# Mako_DSP_Power_R1_2.net
KiCad netlist of a schematic drawn in Altium Designer
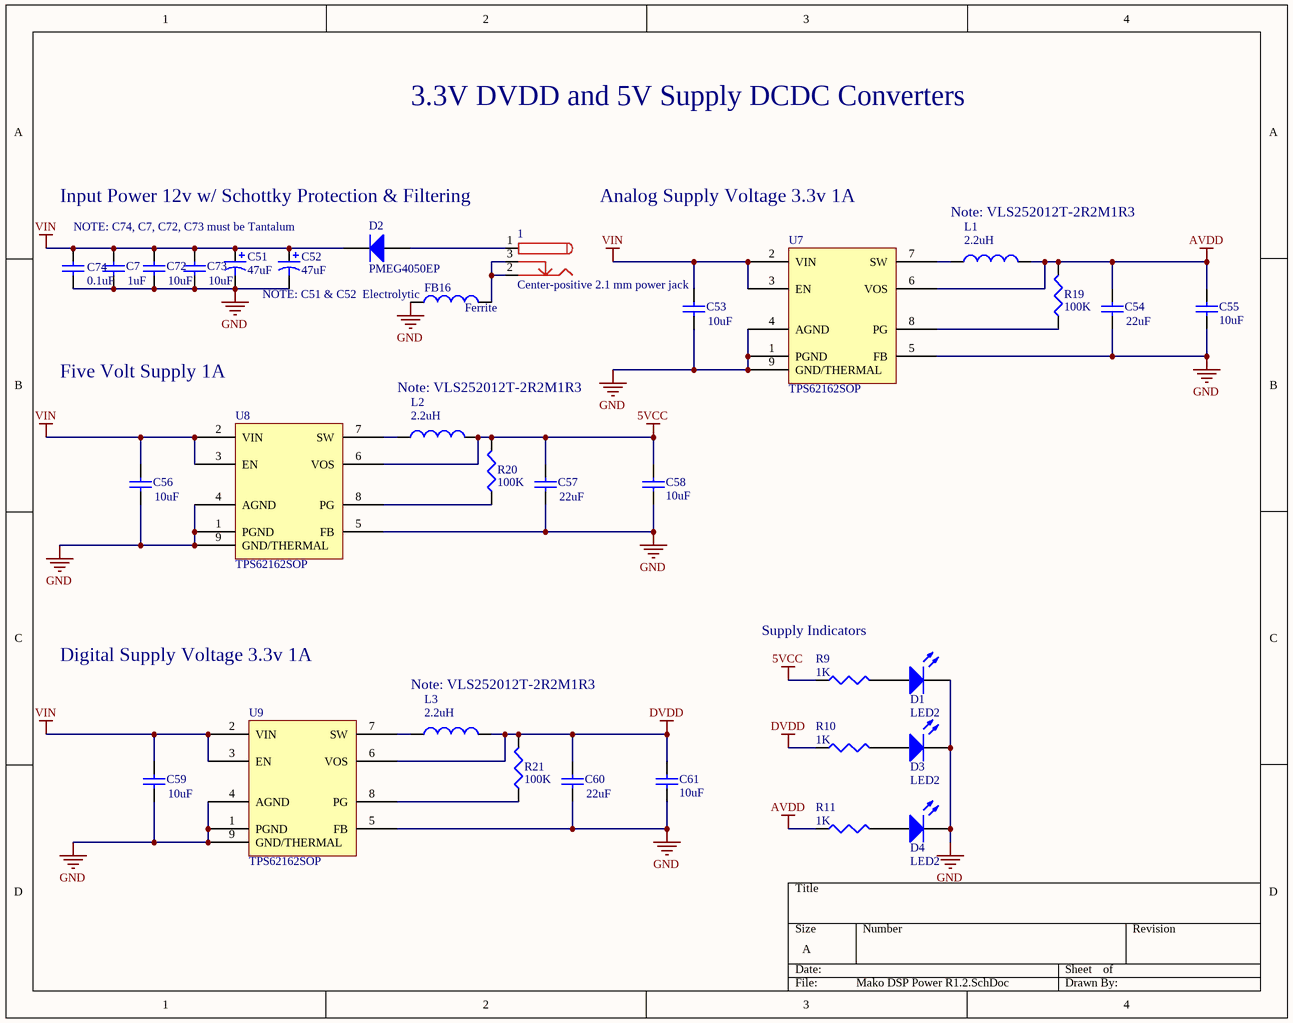
[diagram p0: Mako DSP Power R1.2.SchDoc]

(export (version "E")
  (design (tool "Eeschema 10.0.6"))
  (components
    (comp (ref "1")
      (value "Center-positive 2.1 mm power jack")
      (footprint "PJ-102AH")
      (description "Power jack")
      (fields (field (name "PUBLISHER") "Altium Limited"))
      (libsource (lib "Rascal") (part "PWR2.5"))
    )
    (comp (ref "C7")
      (value "1uF")
      (footprint "C1206")
      (description "Capacitor (Semiconductor SIM Model)")
      (fields (field (name "Comment") "Cap Semi") (field (name "PUBLISHER") "Altium Limited"))
      (libsource (lib "Miscellaneous Devices") (part "Cap Semi"))
    )
    (comp (ref "C51")
      (value "47uF")
      (footprint "CAPPR2.5-6.3x5")
      (description "Polarized Capacitor (Radial)")
      (fields (field (name "Comment") "Cap Pol1") (field (name "PUBLISHER") "Altium Limited"))
      (libsource (lib "Miscellaneous Devices") (part "Cap Pol1"))
    )
    (comp (ref "C52")
      (value "47uF")
      (footprint "CAPPR2.5-6.3x5")
      (description "Polarized Capacitor (Radial)")
      (fields (field (name "Comment") "Cap Pol1") (field (name "PUBLISHER") "Altium Limited"))
      (libsource (lib "Miscellaneous Devices") (part "Cap Pol1"))
    )
    (comp (ref "C53")
      (value "10uF")
      (footprint "C1206")
      (description "Capacitor (Semiconductor SIM Model)")
      (fields (field (name "Comment") "Cap Semi") (field (name "PUBLISHER") "Altium Limited"))
      (libsource (lib "Miscellaneous Devices") (part "Cap Semi"))
    )
    (comp (ref "C54")
      (value "22uF")
      (footprint "C1206")
      (description "Capacitor (Semiconductor SIM Model)")
      (fields (field (name "Comment") "Cap Semi") (field (name "PUBLISHER") "Altium Limited"))
      (libsource (lib "Miscellaneous Devices") (part "Cap Semi"))
    )
    (comp (ref "C55")
      (value "10uF")
      (footprint "Panasonic VS B")
      (description "Capacitor (Semiconductor SIM Model)")
      (fields (field (name "Comment") "Cap Semi") (field (name "PUBLISHER") "Altium Limited"))
      (libsource (lib "Miscellaneous Devices") (part "Cap Semi"))
    )
    (comp (ref "C56")
      (value "10uF")
      (footprint "C1206")
      (description "Capacitor (Semiconductor SIM Model)")
      (fields (field (name "Comment") "Cap Semi") (field (name "PUBLISHER") "Altium Limited"))
      (libsource (lib "Miscellaneous Devices") (part "Cap Semi"))
    )
    (comp (ref "C57")
      (value "22uF")
      (footprint "C1206")
      (description "Capacitor (Semiconductor SIM Model)")
      (fields (field (name "Comment") "Cap Semi") (field (name "PUBLISHER") "Altium Limited"))
      (libsource (lib "Miscellaneous Devices") (part "Cap Semi"))
    )
    (comp (ref "C58")
      (value "10uF")
      (footprint "Panasonic VS B")
      (description "Capacitor (Semiconductor SIM Model)")
      (fields (field (name "Comment") "Cap Semi") (field (name "PUBLISHER") "Altium Limited"))
      (libsource (lib "Miscellaneous Devices") (part "Cap Semi"))
    )
    (comp (ref "C59")
      (value "10uF")
      (footprint "C1206")
      (description "Capacitor (Semiconductor SIM Model)")
      (fields (field (name "Comment") "Cap Semi") (field (name "PUBLISHER") "Altium Limited"))
      (libsource (lib "Miscellaneous Devices") (part "Cap Semi"))
    )
    (comp (ref "C60")
      (value "22uF")
      (footprint "C1206")
      (description "Capacitor (Semiconductor SIM Model)")
      (fields (field (name "Comment") "Cap Semi") (field (name "PUBLISHER") "Altium Limited"))
      (libsource (lib "Miscellaneous Devices") (part "Cap Semi"))
    )
    (comp (ref "C61")
      (value "10uF")
      (footprint "Panasonic VS B")
      (description "Capacitor (Semiconductor SIM Model)")
      (fields (field (name "Comment") "Cap Semi") (field (name "PUBLISHER") "Altium Limited"))
      (libsource (lib "Miscellaneous Devices") (part "Cap Semi"))
    )
    (comp (ref "C72")
      (value "10uF")
      (footprint "C1206")
      (description "Capacitor (Semiconductor SIM Model)")
      (fields (field (name "Comment") "Cap Semi") (field (name "PUBLISHER") "Altium Limited"))
      (libsource (lib "Miscellaneous Devices") (part "Cap Semi"))
    )
    (comp (ref "C73")
      (value "10uF")
      (footprint "C1206")
      (description "Capacitor (Semiconductor SIM Model)")
      (fields (field (name "Comment") "Cap Semi") (field (name "PUBLISHER") "Altium Limited"))
      (libsource (lib "Miscellaneous Devices") (part "Cap Semi"))
    )
    (comp (ref "C74")
      (value "0.1uF")
      (footprint "C1206")
      (description "Capacitor (Semiconductor SIM Model)")
      (fields (field (name "Comment") "Cap Semi") (field (name "PUBLISHER") "Altium Limited"))
      (libsource (lib "Miscellaneous Devices") (part "Cap Semi"))
    )
    (comp (ref "D1")
      (value "LED2")
      (footprint "SM 0805 polarized")
      (description "Typical RED, GREEN, YELLOW, AMBER GaAs LED")
      (fields (field (name "PUBLISHER") "Altium Limited"))
      (libsource (lib "Miscellaneous Devices") (part "LED2"))
    )
    (comp (ref "D2")
      (value "PMEG4050EP")
      (footprint "PMEG4050EP")
      (description "Default Diode")
      (fields (field (name "PUBLISHER") "Altium Limited"))
      (libsource (lib "Miscellaneous Devices") (part "Diode"))
    )
    (comp (ref "D3")
      (value "LED2")
      (footprint "SM 0805 polarized")
      (description "Typical RED, GREEN, YELLOW, AMBER GaAs LED")
      (fields (field (name "PUBLISHER") "Altium Limited"))
      (libsource (lib "Miscellaneous Devices") (part "LED2"))
    )
    (comp (ref "D4")
      (value "LED2")
      (footprint "SM 0805 polarized")
      (description "Typical RED, GREEN, YELLOW, AMBER GaAs LED")
      (fields (field (name "PUBLISHER") "Altium Limited"))
      (libsource (lib "Miscellaneous Devices") (part "LED2"))
    )
    (comp (ref "FB16")
      (value "Ferrite")
      (footprint "SM 0805 - gap trimmed")
      (description "Inductor")
      (fields (field (name "PUBLISHER") "Altium Limited"))
      (libsource (lib "Miscellaneous Devices") (part "Inductor"))
    )
    (comp (ref "L1")
      (value "2.2uH")
      (footprint "VLS252012T-2R2M1R3")
      (description "Inductor")
      (fields (field (name "PUBLISHER") "Altium Limited"))
      (libsource (lib "Miscellaneous Devices") (part "Inductor"))
    )
    (comp (ref "L2")
      (value "2.2uH")
      (footprint "VLS252012T-2R2M1R3")
      (description "Inductor")
      (fields (field (name "PUBLISHER") "Altium Limited"))
      (libsource (lib "Miscellaneous Devices") (part "Inductor"))
    )
    (comp (ref "L3")
      (value "2.2uH")
      (footprint "VLS252012T-2R2M1R3")
      (description "Inductor")
      (fields (field (name "PUBLISHER") "Altium Limited"))
      (libsource (lib "Miscellaneous Devices") (part "Inductor"))
    )
    (comp (ref "R9")
      (value "1K")
      (footprint "J1-0603")
      (description "Resistor")
      (fields (field (name "Comment") "Res3") (field (name "PUBLISHER") "Altium Limited"))
      (libsource (lib "Miscellaneous Devices") (part "Res3"))
    )
    (comp (ref "R10")
      (value "1K")
      (footprint "J1-0603")
      (description "Resistor")
      (fields (field (name "Comment") "Res3") (field (name "PUBLISHER") "Altium Limited"))
      (libsource (lib "Miscellaneous Devices") (part "Res3"))
    )
    (comp (ref "R11")
      (value "1K")
      (footprint "J1-0603")
      (description "Resistor")
      (fields (field (name "Comment") "Res3") (field (name "PUBLISHER") "Altium Limited"))
      (libsource (lib "Miscellaneous Devices") (part "Res3"))
    )
    (comp (ref "R19")
      (value "100K")
      (footprint "RESC2012L")
      (description "Resistor")
      (fields (field (name "Comment") "Res3") (field (name "PUBLISHER") "Altium Limited"))
      (libsource (lib "Miscellaneous Devices") (part "Res3"))
    )
    (comp (ref "R20")
      (value "100K")
      (footprint "RESC2012L")
      (description "Resistor")
      (fields (field (name "Comment") "Res3") (field (name "PUBLISHER") "Altium Limited"))
      (libsource (lib "Miscellaneous Devices") (part "Res3"))
    )
    (comp (ref "R21")
      (value "100K")
      (footprint "RESC2012L")
      (description "Resistor")
      (fields (field (name "Comment") "Res3") (field (name "PUBLISHER") "Altium Limited"))
      (libsource (lib "Miscellaneous Devices") (part "Res3"))
    )
    (comp (ref "U7")
      (value "TPS62162SOP")
      (footprint "TPS62162SOP")
      (libsource (lib "Adams Altium Library") (part "TPS62162SOP"))
    )
    (comp (ref "U8")
      (value "TPS62162SOP")
      (footprint "TPS62162SOP")
      (libsource (lib "Adams Altium Library") (part "TPS62162SOP"))
    )
    (comp (ref "U9")
      (value "TPS62162SOP")
      (footprint "TPS62162SOP")
      (libsource (lib "Adams Altium Library") (part "TPS62162SOP"))
    )
  )
  (nets
    (net (code "1") (name "5VCC") (class "Default")
      (node (ref "C57") (pin "2") (pinfunction "2_2") (pintype "passive"))
      (node (ref "C58") (pin "1") (pinfunction "1_1") (pintype "passive"))
      (node (ref "L2") (pin "2") (pinfunction "2_2") (pintype "passive"))
      (node (ref "R20") (pin "2") (pinfunction "2_2") (pintype "passive"))
      (node (ref "R9") (pin "1") (pinfunction "1_1") (pintype "passive"))
      (node (ref "U8") (pin "6") (pinfunction "VOS_6") (pintype "passive"))
    )
    (net (code "2") (name "AVDD") (class "Default")
      (node (ref "C54") (pin "2") (pinfunction "2_2") (pintype "passive"))
      (node (ref "C55") (pin "1") (pinfunction "1_1") (pintype "passive"))
      (node (ref "L1") (pin "2") (pinfunction "2_2") (pintype "passive"))
      (node (ref "R11") (pin "1") (pinfunction "1_1") (pintype "passive"))
      (node (ref "R19") (pin "2") (pinfunction "2_2") (pintype "passive"))
      (node (ref "U7") (pin "6") (pinfunction "VOS_6") (pintype "passive"))
    )
    (net (code "3") (name "DVDD") (class "Default")
      (node (ref "C60") (pin "2") (pinfunction "2_2") (pintype "passive"))
      (node (ref "C61") (pin "1") (pinfunction "1_1") (pintype "passive"))
      (node (ref "L3") (pin "2") (pinfunction "2_2") (pintype "passive"))
      (node (ref "R10") (pin "1") (pinfunction "1_1") (pintype "passive"))
      (node (ref "R21") (pin "2") (pinfunction "2_2") (pintype "passive"))
      (node (ref "U9") (pin "6") (pinfunction "VOS_6") (pintype "passive"))
    )
    (net (code "4") (name "GND") (class "Default")
      (node (ref "C51") (pin "2") (pinfunction "2_2") (pintype "passive"))
      (node (ref "C52") (pin "2") (pinfunction "2_2") (pintype "passive"))
      (node (ref "C53") (pin "1") (pinfunction "1_1") (pintype "passive"))
      (node (ref "C54") (pin "1") (pinfunction "1_1") (pintype "passive"))
      (node (ref "C55") (pin "2") (pinfunction "2_2") (pintype "passive"))
      (node (ref "C56") (pin "1") (pinfunction "1_1") (pintype "passive"))
      (node (ref "C57") (pin "1") (pinfunction "1_1") (pintype "passive"))
      (node (ref "C58") (pin "2") (pinfunction "2_2") (pintype "passive"))
      (node (ref "C59") (pin "1") (pinfunction "1_1") (pintype "passive"))
      (node (ref "C60") (pin "1") (pinfunction "1_1") (pintype "passive"))
      (node (ref "C61") (pin "2") (pinfunction "2_2") (pintype "passive"))
      (node (ref "C7") (pin "1") (pinfunction "1_1") (pintype "passive"))
      (node (ref "C72") (pin "1") (pinfunction "1_1") (pintype "passive"))
      (node (ref "C73") (pin "1") (pinfunction "1_1") (pintype "passive"))
      (node (ref "C74") (pin "1") (pinfunction "1_1") (pintype "passive"))
      (node (ref "D1") (pin "1") (pinfunction "A_1") (pintype "passive"))
      (node (ref "D3") (pin "1") (pinfunction "A_1") (pintype "passive"))
      (node (ref "D4") (pin "1") (pinfunction "A_1") (pintype "passive"))
      (node (ref "FB16") (pin "1") (pinfunction "1_1") (pintype "passive"))
      (node (ref "U7") (pin "1") (pinfunction "PGND_1") (pintype "passive"))
      (node (ref "U7") (pin "4") (pinfunction "AGND_4") (pintype "passive"))
      (node (ref "U7") (pin "5") (pinfunction "FB_5") (pintype "passive"))
      (node (ref "U7") (pin "9") (pinfunction "GND/THERMAL_9") (pintype "passive"))
      (node (ref "U8") (pin "1") (pinfunction "PGND_1") (pintype "passive"))
      (node (ref "U8") (pin "4") (pinfunction "AGND_4") (pintype "passive"))
      (node (ref "U8") (pin "5") (pinfunction "FB_5") (pintype "passive"))
      (node (ref "U8") (pin "9") (pinfunction "GND/THERMAL_9") (pintype "passive"))
      (node (ref "U9") (pin "1") (pinfunction "PGND_1") (pintype "passive"))
      (node (ref "U9") (pin "4") (pinfunction "AGND_4") (pintype "passive"))
      (node (ref "U9") (pin "5") (pinfunction "FB_5") (pintype "passive"))
      (node (ref "U9") (pin "9") (pinfunction "GND/THERMAL_9") (pintype "passive"))
    )
    (net (code "5") (name "Net-(1-Pad2)") (class "Default")
      (node (ref "1") (pin "2") (pinfunction "2_2") (pintype "power_in"))
      (node (ref "1") (pin "3") (pinfunction "3_3") (pintype "power_in"))
      (node (ref "FB16") (pin "2") (pinfunction "2_2") (pintype "passive"))
    )
    (net (code "6") (name "Net-(D1-K)") (class "Default")
      (node (ref "D1") (pin "2") (pinfunction "K_2") (pintype "passive"))
      (node (ref "R9") (pin "2") (pinfunction "2_2") (pintype "passive"))
    )
    (net (code "7") (name "Net-(D2-K)") (class "Default")
      (node (ref "1") (pin "1") (pinfunction "1_1") (pintype "power_in"))
      (node (ref "D2") (pin "2") (pinfunction "K_2") (pintype "passive"))
    )
    (net (code "8") (name "Net-(D3-K)") (class "Default")
      (node (ref "D3") (pin "2") (pinfunction "K_2") (pintype "passive"))
      (node (ref "R10") (pin "2") (pinfunction "2_2") (pintype "passive"))
    )
    (net (code "9") (name "Net-(D4-K)") (class "Default")
      (node (ref "D4") (pin "2") (pinfunction "K_2") (pintype "passive"))
      (node (ref "R11") (pin "2") (pinfunction "2_2") (pintype "passive"))
    )
    (net (code "10") (name "Net-(U7-PG)") (class "Default")
      (node (ref "R19") (pin "1") (pinfunction "1_1") (pintype "passive"))
      (node (ref "U7") (pin "8") (pinfunction "PG_8") (pintype "passive"))
    )
    (net (code "11") (name "Net-(U7-SW)") (class "Default")
      (node (ref "L1") (pin "1") (pinfunction "1_1") (pintype "passive"))
      (node (ref "U7") (pin "7") (pinfunction "SW_7") (pintype "passive"))
    )
    (net (code "12") (name "Net-(U8-PG)") (class "Default")
      (node (ref "R20") (pin "1") (pinfunction "1_1") (pintype "passive"))
      (node (ref "U8") (pin "8") (pinfunction "PG_8") (pintype "passive"))
    )
    (net (code "13") (name "Net-(U8-SW)") (class "Default")
      (node (ref "L2") (pin "1") (pinfunction "1_1") (pintype "passive"))
      (node (ref "U8") (pin "7") (pinfunction "SW_7") (pintype "passive"))
    )
    (net (code "14") (name "Net-(U9-PG)") (class "Default")
      (node (ref "R21") (pin "1") (pinfunction "1_1") (pintype "passive"))
      (node (ref "U9") (pin "8") (pinfunction "PG_8") (pintype "passive"))
    )
    (net (code "15") (name "Net-(U9-SW)") (class "Default")
      (node (ref "L3") (pin "1") (pinfunction "1_1") (pintype "passive"))
      (node (ref "U9") (pin "7") (pinfunction "SW_7") (pintype "passive"))
    )
    (net (code "16") (name "VIN") (class "Default")
      (node (ref "C51") (pin "1") (pinfunction "1_1") (pintype "passive"))
      (node (ref "C52") (pin "1") (pinfunction "1_1") (pintype "passive"))
      (node (ref "C53") (pin "2") (pinfunction "2_2") (pintype "passive"))
      (node (ref "C56") (pin "2") (pinfunction "2_2") (pintype "passive"))
      (node (ref "C59") (pin "2") (pinfunction "2_2") (pintype "passive"))
      (node (ref "C7") (pin "2") (pinfunction "2_2") (pintype "passive"))
      (node (ref "C72") (pin "2") (pinfunction "2_2") (pintype "passive"))
      (node (ref "C73") (pin "2") (pinfunction "2_2") (pintype "passive"))
      (node (ref "C74") (pin "2") (pinfunction "2_2") (pintype "passive"))
      (node (ref "D2") (pin "1") (pinfunction "A_1") (pintype "passive"))
      (node (ref "U7") (pin "2") (pinfunction "VIN_2") (pintype "passive"))
      (node (ref "U7") (pin "3") (pinfunction "EN_3") (pintype "passive"))
      (node (ref "U8") (pin "2") (pinfunction "VIN_2") (pintype "passive"))
      (node (ref "U8") (pin "3") (pinfunction "EN_3") (pintype "passive"))
      (node (ref "U9") (pin "2") (pinfunction "VIN_2") (pintype "passive"))
      (node (ref "U9") (pin "3") (pinfunction "EN_3") (pintype "passive"))
    )
  )
)
